# MB.net
KiCad netlist of a schematic drawn in Altium Designer
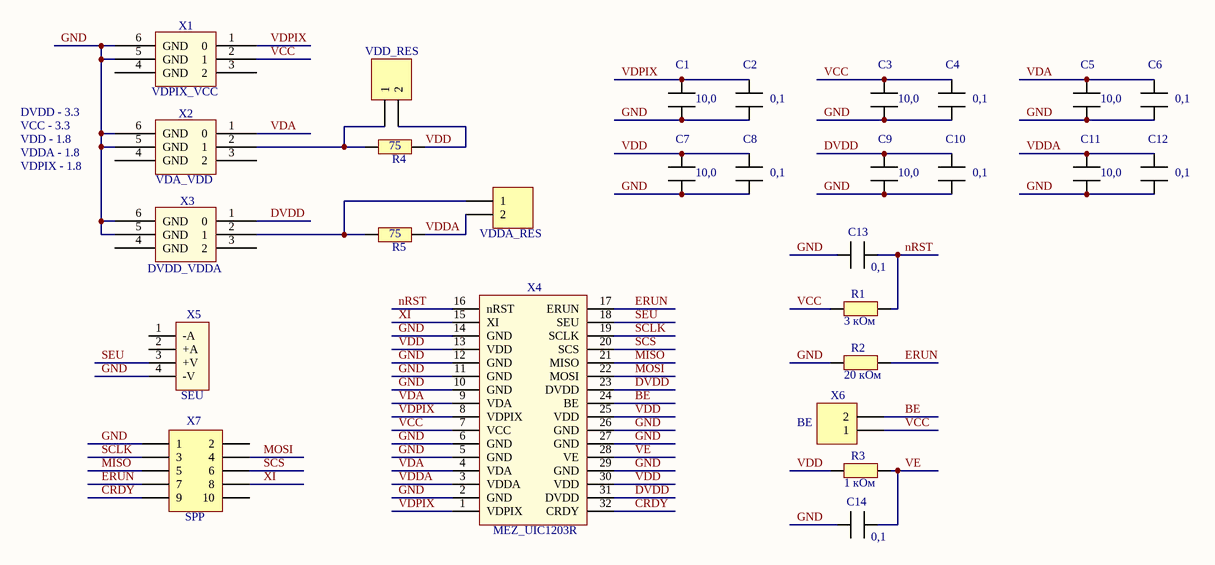
[diagram p0: MB.SchDoc]

(export (version "E")
  (design (tool "Eeschema 10.0.6"))
  (components
    (comp (ref "C1") (value "10,0") (footprint "Cap_BIG") (libsource (lib "Schlib") (part "CAP_BIG")))
    (comp (ref "C2") (value "0,1") (footprint "CAP_SMALL") (libsource (lib "Schlib") (part "CAP_SMALL")))
    (comp (ref "C3") (value "10,0") (footprint "Cap_BIG") (libsource (lib "Schlib") (part "CAP_BIG")))
    (comp (ref "C4") (value "0,1") (footprint "CAP_SMALL") (libsource (lib "Schlib") (part "CAP_SMALL")))
    (comp (ref "C5") (value "10,0") (footprint "Cap_BIG") (libsource (lib "Schlib") (part "CAP_BIG")))
    (comp (ref "C6") (value "0,1") (footprint "CAP_SMALL") (libsource (lib "Schlib") (part "CAP_SMALL")))
    (comp (ref "C7") (value "10,0") (footprint "Cap_BIG") (libsource (lib "Schlib") (part "CAP_BIG")))
    (comp (ref "C8") (value "0,1") (footprint "CAP_SMALL") (libsource (lib "Schlib") (part "CAP_SMALL")))
    (comp (ref "C9") (value "10,0") (footprint "Cap_BIG") (libsource (lib "Schlib") (part "CAP_BIG")))
    (comp (ref "C10") (value "0,1") (footprint "CAP_SMALL") (libsource (lib "Schlib") (part "CAP_SMALL")))
    (comp (ref "C11") (value "10,0") (footprint "Cap_BIG") (libsource (lib "Schlib") (part "CAP_BIG")))
    (comp (ref "C12") (value "0,1") (footprint "CAP_SMALL") (libsource (lib "Schlib") (part "CAP_SMALL")))
    (comp (ref "C13") (value "0,1") (footprint "CAP_SMALL") (libsource (lib "Schlib") (part "CAP_SMALL")))
    (comp (ref "C14") (value "0,1") (footprint "CAP_SMALL") (libsource (lib "Schlib") (part "CAP_SMALL")))
    (comp (ref "R1") (value "3 кОм") (footprint "RES") (libsource (lib "Schlib") (part "RES")))
    (comp (ref "R2") (value "20 кОм") (footprint "RES") (libsource (lib "Schlib") (part "RES")))
    (comp (ref "R3") (value "1 кОм") (footprint "RES") (libsource (lib "Schlib") (part "RES")))
    (comp (ref "R4") (value "75") (footprint "RES") (libsource (lib "Schlib") (part "RES")))
    (comp (ref "R5") (value "75") (footprint "RES") (libsource (lib "Schlib") (part "RES")))
    (comp (ref "VDDA_RES")
      (value "Header 2")
      (footprint "HDR1X2")
      (description "Header, 2-Pin")
      (fields (field (name "PUBLISHER") "Altium Limited"))
      (libsource (lib "Miscellaneous Connectors") (part "Header 2"))
    )
    (comp (ref "VDD_RES")
      (value "Header 2")
      (footprint "HDR1X2")
      (description "Header, 2-Pin")
      (fields (field (name "PUBLISHER") "Altium Limited"))
      (libsource (lib "") (part "Header 2_2"))
    )
    (comp (ref "X1") (value "VDPIX_VCC") (footprint "POWER") (libsource (lib "Schlib") (part "POWER")))
    (comp (ref "X2") (value "VDA_VDD") (footprint "POWER") (libsource (lib "Schlib") (part "POWER")))
    (comp (ref "X3") (value "DVDD_VDDA") (footprint "POWER") (libsource (lib "Schlib") (part "POWER")))
    (comp (ref "X4")
      (value "MEZ_UIC1203R")
      (footprint "MEZ_UIC1203R")
      (libsource (lib "Schlib") (part "MEZ_UIC1203R"))
    )
    (comp (ref "X5")
      (value "SEU")
      (footprint "AMP_VOLTMETER")
      (libsource (lib "Schlib") (part "AMP_VOLTMETER"))
    )
    (comp (ref "X6")
      (value "BE")
      (footprint "HDR1X2")
      (description "Header, 2-Pin")
      (fields (field (name "PUBLISHER") "Altium Limited"))
      (libsource (lib "") (part "Header 2_1"))
    )
    (comp (ref "X7")
      (value "SPP")
      (footprint "HDR2X5")
      (description "Header, 5-Pin, Dual row")
      (fields (field (name "PUBLISHER") "Altium Limited"))
      (libsource (lib "Miscellaneous Connectors") (part "Header 5X2"))
    )
  )
  (nets
    (net (code "1") (name "/BE") (class "Default")
      (node (ref "X4") (pin "24") (pinfunction "BE_24") (pintype "passive"))
      (node (ref "X6") (pin "2") (pinfunction "2_2") (pintype "passive"))
    )
    (net (code "2") (name "/CRDY") (class "Default")
      (node (ref "X4") (pin "32") (pinfunction "CRDY_32") (pintype "passive"))
      (node (ref "X7") (pin "9") (pinfunction "9_9") (pintype "passive"))
    )
    (net (code "3") (name "/DVDD") (class "Default")
      (node (ref "C10") (pin "2") (pinfunction "2_2") (pintype "passive"))
      (node (ref "C9") (pin "2") (pinfunction "2_2") (pintype "passive"))
      (node (ref "X3") (pin "1") (pinfunction "0_1") (pintype "passive"))
      (node (ref "X4") (pin "23") (pinfunction "DVDD_23") (pintype "passive"))
      (node (ref "X4") (pin "31") (pinfunction "DVDD_31") (pintype "passive"))
    )
    (net (code "4") (name "/ERUN") (class "Default")
      (node (ref "R2") (pin "2") (pinfunction "2_2") (pintype "passive"))
      (node (ref "X4") (pin "17") (pinfunction "ERUN_17") (pintype "passive"))
      (node (ref "X7") (pin "7") (pinfunction "7_7") (pintype "passive"))
    )
    (net (code "5") (name "/GND") (class "Default")
      (node (ref "C1") (pin "1") (pinfunction "1_1") (pintype "passive"))
      (node (ref "C10") (pin "1") (pinfunction "1_1") (pintype "passive"))
      (node (ref "C11") (pin "1") (pinfunction "1_1") (pintype "passive"))
      (node (ref "C12") (pin "1") (pinfunction "1_1") (pintype "passive"))
      (node (ref "C13") (pin "2") (pinfunction "2_2") (pintype "passive"))
      (node (ref "C14") (pin "2") (pinfunction "2_2") (pintype "passive"))
      (node (ref "C2") (pin "1") (pinfunction "1_1") (pintype "passive"))
      (node (ref "C3") (pin "1") (pinfunction "1_1") (pintype "passive"))
      (node (ref "C4") (pin "1") (pinfunction "1_1") (pintype "passive"))
      (node (ref "C5") (pin "1") (pinfunction "1_1") (pintype "passive"))
      (node (ref "C6") (pin "1") (pinfunction "1_1") (pintype "passive"))
      (node (ref "C7") (pin "1") (pinfunction "1_1") (pintype "passive"))
      (node (ref "C8") (pin "1") (pinfunction "1_1") (pintype "passive"))
      (node (ref "C9") (pin "1") (pinfunction "1_1") (pintype "passive"))
      (node (ref "R2") (pin "1") (pinfunction "1_1") (pintype "passive"))
      (node (ref "X1") (pin "5") (pinfunction "GND_5") (pintype "passive"))
      (node (ref "X1") (pin "6") (pinfunction "GND_6") (pintype "passive"))
      (node (ref "X2") (pin "5") (pinfunction "GND_5") (pintype "passive"))
      (node (ref "X2") (pin "6") (pinfunction "GND_6") (pintype "passive"))
      (node (ref "X3") (pin "5") (pinfunction "GND_5") (pintype "passive"))
      (node (ref "X3") (pin "6") (pinfunction "GND_6") (pintype "passive"))
      (node (ref "X4") (pin "10") (pinfunction "GND_10") (pintype "passive"))
      (node (ref "X4") (pin "11") (pinfunction "GND_11") (pintype "passive"))
      (node (ref "X4") (pin "12") (pinfunction "GND_12") (pintype "passive"))
      (node (ref "X4") (pin "14") (pinfunction "GND_14") (pintype "passive"))
      (node (ref "X4") (pin "2") (pinfunction "GND_2") (pintype "passive"))
      (node (ref "X4") (pin "26") (pinfunction "GND_26") (pintype "passive"))
      (node (ref "X4") (pin "27") (pinfunction "GND_27") (pintype "passive"))
      (node (ref "X4") (pin "29") (pinfunction "GND_29") (pintype "passive"))
      (node (ref "X4") (pin "5") (pinfunction "GND_5") (pintype "passive"))
      (node (ref "X4") (pin "6") (pinfunction "GND_6") (pintype "passive"))
      (node (ref "X5") (pin "4") (pinfunction "-V_4") (pintype "passive"))
      (node (ref "X7") (pin "1") (pinfunction "1_1") (pintype "passive"))
    )
    (net (code "6") (name "/MISO") (class "Default")
      (node (ref "X4") (pin "21") (pinfunction "MISO_21") (pintype "passive"))
      (node (ref "X7") (pin "5") (pinfunction "5_5") (pintype "passive"))
    )
    (net (code "7") (name "/MOSI") (class "Default")
      (node (ref "X4") (pin "22") (pinfunction "MOSI_22") (pintype "passive"))
      (node (ref "X7") (pin "4") (pinfunction "4_4") (pintype "passive"))
    )
    (net (code "8") (name "/SCLK") (class "Default")
      (node (ref "X4") (pin "19") (pinfunction "SCLK_19") (pintype "passive"))
      (node (ref "X7") (pin "3") (pinfunction "3_3") (pintype "passive"))
    )
    (net (code "9") (name "/SCS") (class "Default")
      (node (ref "X4") (pin "20") (pinfunction "SCS_20") (pintype "passive"))
      (node (ref "X7") (pin "6") (pinfunction "6_6") (pintype "passive"))
    )
    (net (code "10") (name "/SEU") (class "Default")
      (node (ref "X4") (pin "18") (pinfunction "SEU_18") (pintype "passive"))
      (node (ref "X5") (pin "3") (pinfunction "+V_3") (pintype "passive"))
    )
    (net (code "11") (name "/VCC") (class "Default")
      (node (ref "C3") (pin "2") (pinfunction "2_2") (pintype "passive"))
      (node (ref "C4") (pin "2") (pinfunction "2_2") (pintype "passive"))
      (node (ref "R1") (pin "1") (pinfunction "1_1") (pintype "passive"))
      (node (ref "X1") (pin "2") (pinfunction "1_2") (pintype "passive"))
      (node (ref "X4") (pin "7") (pinfunction "VCC_7") (pintype "passive"))
      (node (ref "X6") (pin "1") (pinfunction "1_1") (pintype "passive"))
    )
    (net (code "12") (name "/VDA") (class "Default")
      (node (ref "C5") (pin "2") (pinfunction "2_2") (pintype "passive"))
      (node (ref "C6") (pin "2") (pinfunction "2_2") (pintype "passive"))
      (node (ref "X2") (pin "1") (pinfunction "0_1") (pintype "passive"))
      (node (ref "X4") (pin "4") (pinfunction "VDA_4") (pintype "passive"))
      (node (ref "X4") (pin "9") (pinfunction "VDA_9") (pintype "passive"))
    )
    (net (code "13") (name "/VDD") (class "Default")
      (node (ref "C7") (pin "2") (pinfunction "2_2") (pintype "passive"))
      (node (ref "C8") (pin "2") (pinfunction "2_2") (pintype "passive"))
      (node (ref "R3") (pin "1") (pinfunction "1_1") (pintype "passive"))
      (node (ref "R4") (pin "2") (pinfunction "2_2") (pintype "passive"))
      (node (ref "VDD_RES") (pin "2") (pinfunction "2_2") (pintype "passive"))
      (node (ref "X4") (pin "13") (pinfunction "VDD_13") (pintype "passive"))
      (node (ref "X4") (pin "25") (pinfunction "VDD_25") (pintype "passive"))
      (node (ref "X4") (pin "30") (pinfunction "VDD_30") (pintype "passive"))
    )
    (net (code "14") (name "/VDDA") (class "Default")
      (node (ref "C11") (pin "2") (pinfunction "2_2") (pintype "passive"))
      (node (ref "C12") (pin "2") (pinfunction "2_2") (pintype "passive"))
      (node (ref "R5") (pin "2") (pinfunction "2_2") (pintype "passive"))
      (node (ref "VDDA_RES") (pin "2") (pinfunction "2_2") (pintype "passive"))
      (node (ref "X4") (pin "3") (pinfunction "VDDA_3") (pintype "passive"))
    )
    (net (code "15") (name "/VDPIX") (class "Default")
      (node (ref "C1") (pin "2") (pinfunction "2_2") (pintype "passive"))
      (node (ref "C2") (pin "2") (pinfunction "2_2") (pintype "passive"))
      (node (ref "X1") (pin "1") (pinfunction "0_1") (pintype "passive"))
      (node (ref "X4") (pin "1") (pinfunction "VDPIX_1") (pintype "passive"))
      (node (ref "X4") (pin "8") (pinfunction "VDPIX_8") (pintype "passive"))
    )
    (net (code "16") (name "/VE") (class "Default")
      (node (ref "C14") (pin "1") (pinfunction "1_1") (pintype "passive"))
      (node (ref "R3") (pin "2") (pinfunction "2_2") (pintype "passive"))
      (node (ref "X4") (pin "28") (pinfunction "VE_28") (pintype "passive"))
    )
    (net (code "17") (name "/XI") (class "Default")
      (node (ref "X4") (pin "15") (pinfunction "XI_15") (pintype "passive"))
      (node (ref "X7") (pin "8") (pinfunction "8_8") (pintype "passive"))
    )
    (net (code "18") (name "/nRST") (class "Default")
      (node (ref "C13") (pin "1") (pinfunction "1_1") (pintype "passive"))
      (node (ref "R1") (pin "2") (pinfunction "2_2") (pintype "passive"))
      (node (ref "X4") (pin "16") (pinfunction "nRST_16") (pintype "passive"))
    )
    (net (code "19") (name "Net-(X2-1)") (class "Default")
      (node (ref "R4") (pin "1") (pinfunction "1_1") (pintype "passive"))
      (node (ref "VDD_RES") (pin "1") (pinfunction "1_1") (pintype "passive"))
      (node (ref "X2") (pin "2") (pinfunction "1_2") (pintype "passive"))
    )
    (net (code "20") (name "Net-(X3-1)") (class "Default")
      (node (ref "R5") (pin "1") (pinfunction "1_1") (pintype "passive"))
      (node (ref "VDDA_RES") (pin "1") (pinfunction "1_1") (pintype "passive"))
      (node (ref "X3") (pin "2") (pinfunction "1_2") (pintype "passive"))
    )
    (net (code "21") (name "unconnected-(X1-2-Pad3)") (class "Default")
      (node (ref "X1") (pin "3") (pinfunction "2_3") (pintype "passive"))
    )
    (net (code "22") (name "unconnected-(X1-GND-Pad4)") (class "Default")
      (node (ref "X1") (pin "4") (pinfunction "GND_4") (pintype "passive"))
    )
    (net (code "23") (name "unconnected-(X2-2-Pad3)") (class "Default")
      (node (ref "X2") (pin "3") (pinfunction "2_3") (pintype "passive"))
    )
    (net (code "24") (name "unconnected-(X2-GND-Pad4)") (class "Default")
      (node (ref "X2") (pin "4") (pinfunction "GND_4") (pintype "passive"))
    )
    (net (code "25") (name "unconnected-(X3-2-Pad3)") (class "Default")
      (node (ref "X3") (pin "3") (pinfunction "2_3") (pintype "passive"))
    )
    (net (code "26") (name "unconnected-(X3-GND-Pad4)") (class "Default")
      (node (ref "X3") (pin "4") (pinfunction "GND_4") (pintype "passive"))
    )
    (net (code "27") (name "unconnected-(X5-+A-Pad2)") (class "Default")
      (node (ref "X5") (pin "2") (pinfunction "+A_2") (pintype "passive"))
    )
    (net (code "28") (name "unconnected-(X5--A-Pad1)") (class "Default")
      (node (ref "X5") (pin "1") (pinfunction "-A_1") (pintype "passive"))
    )
    (net (code "29") (name "unconnected-(X7-Pad2)") (class "Default")
      (node (ref "X7") (pin "2") (pinfunction "2_2") (pintype "passive"))
    )
    (net (code "30") (name "unconnected-(X7-Pad10)") (class "Default")
      (node (ref "X7") (pin "10") (pinfunction "10_10") (pintype "passive"))
    )
  )
)
